# HDMI_Bridge.net
KiCad netlist of a schematic drawn in Altium Designer
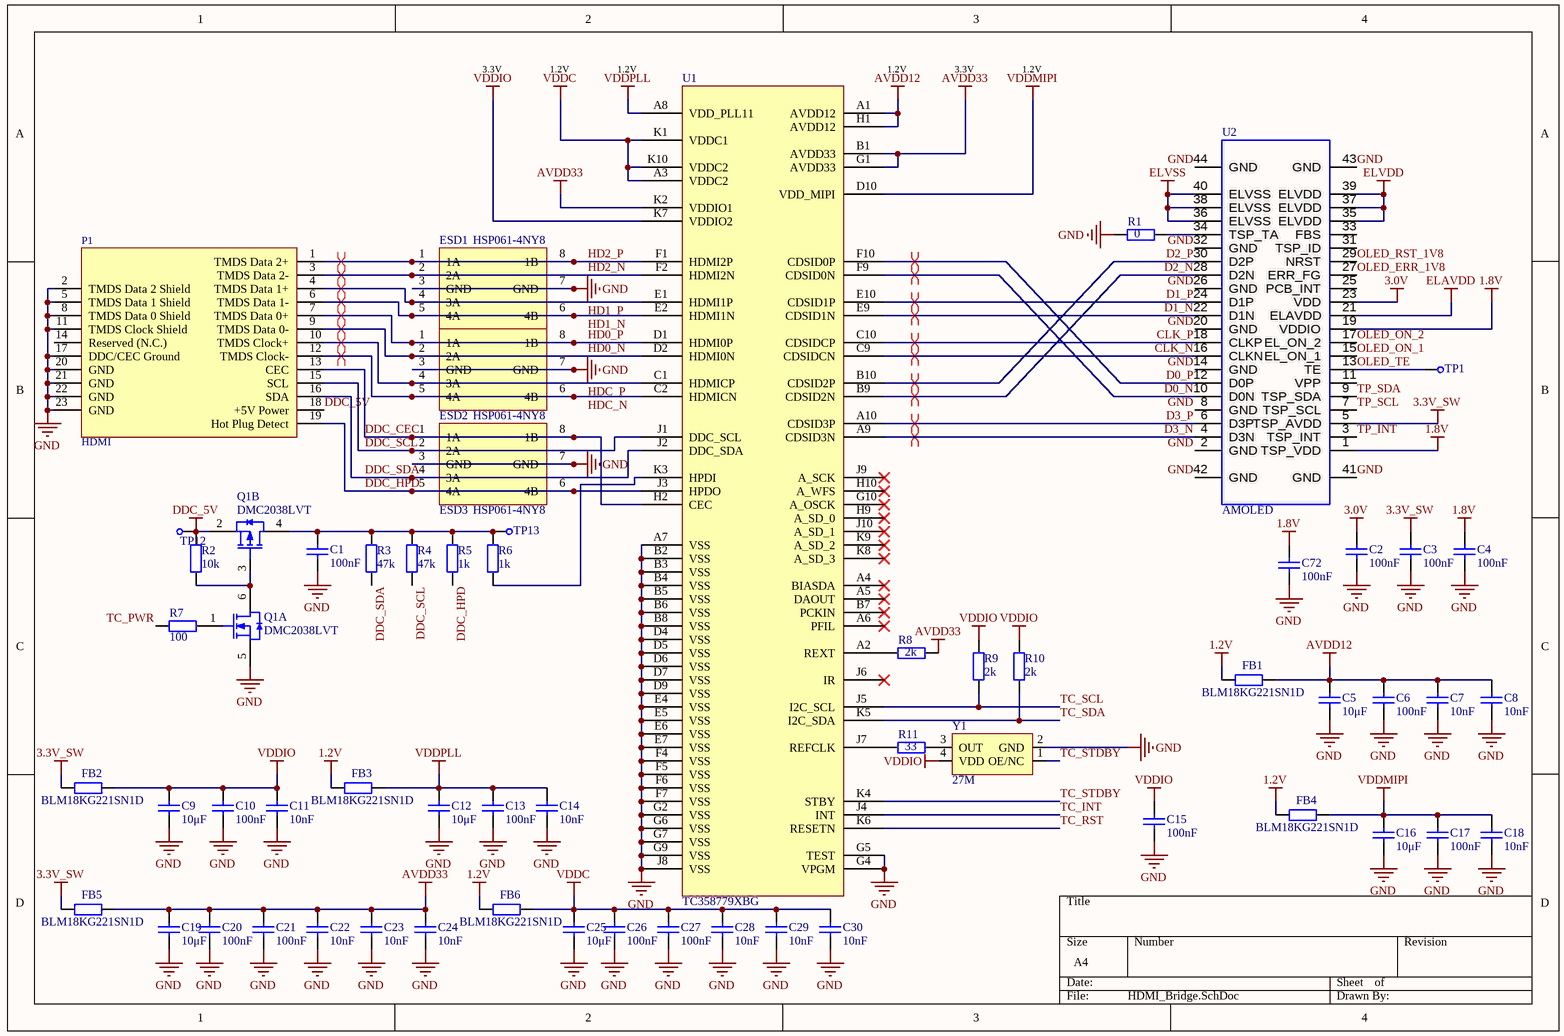
[diagram p0: HDMI_Bridge.SchDoc]

(export (version "E")
  (design (tool "Eeschema 10.0.6"))
  (components
    (comp (ref "C1")
      (value "100nF")
      (footprint "0402C")
      (description "无极性电容")
      (fields (field (name "Comment") "Cap") (field (name "PUBLISHER") "Altium Limited"))
      (libsource (lib "Huskie") (part "Cap"))
    )
    (comp (ref "C2")
      (value "100nF")
      (footprint "0402C")
      (description "无极性电容")
      (fields (field (name "Comment") "Cap") (field (name "PUBLISHER") "Altium Limited"))
      (libsource (lib "Huskie") (part "Cap"))
    )
    (comp (ref "C3")
      (value "100nF")
      (footprint "0402C")
      (description "无极性电容")
      (fields (field (name "Comment") "Cap") (field (name "PUBLISHER") "Altium Limited"))
      (libsource (lib "Huskie") (part "Cap"))
    )
    (comp (ref "C4")
      (value "100nF")
      (footprint "0402C")
      (description "无极性电容")
      (fields (field (name "Comment") "Cap") (field (name "PUBLISHER") "Altium Limited"))
      (libsource (lib "Huskie") (part "Cap"))
    )
    (comp (ref "C5")
      (value "10μF")
      (footprint "0603C")
      (description "无极性电容")
      (fields (field (name "Comment") "Cap") (field (name "PUBLISHER") "Altium Limited"))
      (libsource (lib "Huskie") (part "Cap"))
    )
    (comp (ref "C6")
      (value "100nF")
      (footprint "0402C")
      (description "无极性电容")
      (fields (field (name "Comment") "Cap") (field (name "PUBLISHER") "Altium Limited"))
      (libsource (lib "Huskie") (part "Cap"))
    )
    (comp (ref "C7")
      (value "10nF")
      (footprint "0402C")
      (description "无极性电容")
      (fields (field (name "Comment") "Cap") (field (name "PUBLISHER") "Altium Limited"))
      (libsource (lib "Huskie") (part "Cap"))
    )
    (comp (ref "C8")
      (value "10nF")
      (footprint "0402C")
      (description "无极性电容")
      (fields (field (name "Comment") "Cap") (field (name "PUBLISHER") "Altium Limited"))
      (libsource (lib "Huskie") (part "Cap"))
    )
    (comp (ref "C9")
      (value "10μF")
      (footprint "0603C")
      (description "无极性电容")
      (fields (field (name "Comment") "Cap") (field (name "PUBLISHER") "Altium Limited"))
      (libsource (lib "Huskie") (part "Cap"))
    )
    (comp (ref "C10")
      (value "100nF")
      (footprint "0402C")
      (description "无极性电容")
      (fields (field (name "Comment") "Cap") (field (name "PUBLISHER") "Altium Limited"))
      (libsource (lib "Huskie") (part "Cap"))
    )
    (comp (ref "C11")
      (value "10nF")
      (footprint "0402C")
      (description "无极性电容")
      (fields (field (name "Comment") "Cap") (field (name "PUBLISHER") "Altium Limited"))
      (libsource (lib "Huskie") (part "Cap"))
    )
    (comp (ref "C12")
      (value "10μF")
      (footprint "0603C")
      (description "无极性电容")
      (fields (field (name "Comment") "Cap") (field (name "PUBLISHER") "Altium Limited"))
      (libsource (lib "Huskie") (part "Cap"))
    )
    (comp (ref "C13")
      (value "100nF")
      (footprint "0402C")
      (description "无极性电容")
      (fields (field (name "Comment") "Cap") (field (name "PUBLISHER") "Altium Limited"))
      (libsource (lib "Huskie") (part "Cap"))
    )
    (comp (ref "C14")
      (value "10nF")
      (footprint "0402C")
      (description "无极性电容")
      (fields (field (name "Comment") "Cap") (field (name "PUBLISHER") "Altium Limited"))
      (libsource (lib "Huskie") (part "Cap"))
    )
    (comp (ref "C15")
      (value "100nF")
      (footprint "0402C")
      (description "无极性电容")
      (fields (field (name "Comment") "Cap") (field (name "PUBLISHER") "Altium Limited"))
      (libsource (lib "Huskie") (part "Cap"))
    )
    (comp (ref "C16")
      (value "10μF")
      (footprint "0603C")
      (description "无极性电容")
      (fields (field (name "Comment") "Cap") (field (name "PUBLISHER") "Altium Limited"))
      (libsource (lib "Huskie") (part "Cap"))
    )
    (comp (ref "C17")
      (value "100nF")
      (footprint "0402C")
      (description "无极性电容")
      (fields (field (name "Comment") "Cap") (field (name "PUBLISHER") "Altium Limited"))
      (libsource (lib "Huskie") (part "Cap"))
    )
    (comp (ref "C18")
      (value "10nF")
      (footprint "0402C")
      (description "无极性电容")
      (fields (field (name "Comment") "Cap") (field (name "PUBLISHER") "Altium Limited"))
      (libsource (lib "Huskie") (part "Cap"))
    )
    (comp (ref "C19")
      (value "10μF")
      (footprint "0603C")
      (description "无极性电容")
      (fields (field (name "Comment") "Cap") (field (name "PUBLISHER") "Altium Limited"))
      (libsource (lib "Huskie") (part "Cap"))
    )
    (comp (ref "C20")
      (value "100nF")
      (footprint "0402C")
      (description "无极性电容")
      (fields (field (name "Comment") "Cap") (field (name "PUBLISHER") "Altium Limited"))
      (libsource (lib "Huskie") (part "Cap"))
    )
    (comp (ref "C21")
      (value "100nF")
      (footprint "0402C")
      (description "无极性电容")
      (fields (field (name "Comment") "Cap") (field (name "PUBLISHER") "Altium Limited"))
      (libsource (lib "Huskie") (part "Cap"))
    )
    (comp (ref "C22")
      (value "10nF")
      (footprint "0402C")
      (description "无极性电容")
      (fields (field (name "Comment") "Cap") (field (name "PUBLISHER") "Altium Limited"))
      (libsource (lib "Huskie") (part "Cap"))
    )
    (comp (ref "C23")
      (value "10nF")
      (footprint "0402C")
      (description "无极性电容")
      (fields (field (name "Comment") "Cap") (field (name "PUBLISHER") "Altium Limited"))
      (libsource (lib "Huskie") (part "Cap"))
    )
    (comp (ref "C24")
      (value "10nF")
      (footprint "0402C")
      (description "无极性电容")
      (fields (field (name "Comment") "Cap") (field (name "PUBLISHER") "Altium Limited"))
      (libsource (lib "Huskie") (part "Cap"))
    )
    (comp (ref "C25")
      (value "10μF")
      (footprint "0603C")
      (description "无极性电容")
      (fields (field (name "Comment") "Cap") (field (name "PUBLISHER") "Altium Limited"))
      (libsource (lib "Huskie") (part "Cap"))
    )
    (comp (ref "C26")
      (value "100nF")
      (footprint "0402C")
      (description "无极性电容")
      (fields (field (name "Comment") "Cap") (field (name "PUBLISHER") "Altium Limited"))
      (libsource (lib "Huskie") (part "Cap"))
    )
    (comp (ref "C27")
      (value "100nF")
      (footprint "0402C")
      (description "无极性电容")
      (fields (field (name "Comment") "Cap") (field (name "PUBLISHER") "Altium Limited"))
      (libsource (lib "Huskie") (part "Cap"))
    )
    (comp (ref "C28")
      (value "10nF")
      (footprint "0402C")
      (description "无极性电容")
      (fields (field (name "Comment") "Cap") (field (name "PUBLISHER") "Altium Limited"))
      (libsource (lib "Huskie") (part "Cap"))
    )
    (comp (ref "C29")
      (value "10nF")
      (footprint "0402C")
      (description "无极性电容")
      (fields (field (name "Comment") "Cap") (field (name "PUBLISHER") "Altium Limited"))
      (libsource (lib "Huskie") (part "Cap"))
    )
    (comp (ref "C30")
      (value "10nF")
      (footprint "0402C")
      (description "无极性电容")
      (fields (field (name "Comment") "Cap") (field (name "PUBLISHER") "Altium Limited"))
      (libsource (lib "Huskie") (part "Cap"))
    )
    (comp (ref "C72")
      (value "100nF")
      (footprint "0402C")
      (description "无极性电容")
      (fields (field (name "Comment") "Cap") (field (name "PUBLISHER") "Altium Limited"))
      (libsource (lib "Huskie") (part "Cap"))
    )
    (comp (ref "ESD1")
      (value "HSP061-4NY8")
      (footprint "HSP061-4NY8")
      (description "IC, 4-LINE ESD PROTECTION ARRAY, HIGH SPEED")
      (fields (field (name "MANUFACTURER") "STMICROELECTRONICS"))
      (libsource (lib "Huskie") (part "HSP061-4NY8"))
    )
    (comp (ref "ESD2")
      (value "HSP061-4NY8")
      (footprint "HSP061-4NY8")
      (description "IC, 4-LINE ESD PROTECTION ARRAY, HIGH SPEED")
      (fields (field (name "MANUFACTURER") "STMICROELECTRONICS"))
      (libsource (lib "Huskie") (part "HSP061-4NY8"))
    )
    (comp (ref "ESD3")
      (value "HSP061-4NY8")
      (footprint "HSP061-4NY8")
      (description "IC, 4-LINE ESD PROTECTION ARRAY, HIGH SPEED")
      (fields (field (name "MANUFACTURER") "STMICROELECTRONICS"))
      (libsource (lib "Huskie") (part "HSP061-4NY8"))
    )
    (comp (ref "FB1")
      (value "BLM18KG221SN1D")
      (footprint "0603R")
      (description "电阻")
      (fields (field (name "Comment") "Resistor") (field (name "PUBLISHER") "Altium Limited"))
      (libsource (lib "Huskie") (part "Resistor"))
    )
    (comp (ref "FB2")
      (value "BLM18KG221SN1D")
      (footprint "0603R")
      (description "电阻")
      (fields (field (name "Comment") "Resistor") (field (name "PUBLISHER") "Altium Limited"))
      (libsource (lib "Huskie") (part "Resistor"))
    )
    (comp (ref "FB3")
      (value "BLM18KG221SN1D")
      (footprint "0603R")
      (description "电阻")
      (fields (field (name "Comment") "Resistor") (field (name "PUBLISHER") "Altium Limited"))
      (libsource (lib "Huskie") (part "Resistor"))
    )
    (comp (ref "FB4")
      (value "BLM18KG221SN1D")
      (footprint "0603R")
      (description "电阻")
      (fields (field (name "Comment") "Resistor") (field (name "PUBLISHER") "Altium Limited"))
      (libsource (lib "Huskie") (part "Resistor"))
    )
    (comp (ref "FB5")
      (value "BLM18KG221SN1D")
      (footprint "0603R")
      (description "电阻")
      (fields (field (name "Comment") "Resistor") (field (name "PUBLISHER") "Altium Limited"))
      (libsource (lib "Huskie") (part "Resistor"))
    )
    (comp (ref "FB6")
      (value "BLM18KG221SN1D")
      (footprint "0603R")
      (description "电阻")
      (fields (field (name "Comment") "Resistor") (field (name "PUBLISHER") "Altium Limited"))
      (libsource (lib "Huskie") (part "Resistor"))
    )
    (comp (ref "P1")
      (value "HDMI")
      (footprint "HDMI-SMD_HDMI-001S")
      (description "HDMI Slot")
      (fields
        (field (name "BOM_SUPPLIER PART") "C720616")
        (field (name "BOM_MANUFACTURER PART") "HDMI-001S")
        (field (name "CONTRIBUTOR") "LCSC")
      )
      (libsource (lib "Huskie") (part "HDMI-Slot"))
    )
    (comp (ref "Q1")
      (value "DMC2038LVT")
      (footprint "SOT-23-6")
      (description "Dual P + N MOS")
      (libsource (lib "Huskie") (part "DMC2038LVT"))
    )
    (comp (ref "R1")
      (value "0")
      (footprint "0402R")
      (description "电阻")
      (fields (field (name "Comment") "Resistor") (field (name "PUBLISHER") "Altium Limited"))
      (libsource (lib "") (part "Resistor_1"))
    )
    (comp (ref "R2")
      (value "10k")
      (footprint "0402R")
      (description "电阻")
      (fields (field (name "Comment") "Resistor") (field (name "PUBLISHER") "Altium Limited"))
      (libsource (lib "") (part "Resistor_2"))
    )
    (comp (ref "R3")
      (value "47k")
      (footprint "0402R")
      (description "电阻")
      (fields (field (name "Comment") "Resistor") (field (name "PUBLISHER") "Altium Limited"))
      (libsource (lib "") (part "Resistor_2"))
    )
    (comp (ref "R4")
      (value "47k")
      (footprint "0402R")
      (description "电阻")
      (fields (field (name "Comment") "Resistor") (field (name "PUBLISHER") "Altium Limited"))
      (libsource (lib "") (part "Resistor_2"))
    )
    (comp (ref "R5")
      (value "1k")
      (footprint "0402R")
      (description "电阻")
      (fields (field (name "Comment") "Resistor") (field (name "PUBLISHER") "Altium Limited"))
      (libsource (lib "") (part "Resistor_2"))
    )
    (comp (ref "R6")
      (value "1k")
      (footprint "0402R")
      (description "电阻")
      (fields (field (name "Comment") "Resistor") (field (name "PUBLISHER") "Altium Limited"))
      (libsource (lib "") (part "Resistor_2"))
    )
    (comp (ref "R7")
      (value "100")
      (footprint "0402R")
      (description "电阻")
      (fields (field (name "Comment") "Resistor") (field (name "PUBLISHER") "Altium Limited"))
      (libsource (lib "Huskie") (part "Resistor"))
    )
    (comp (ref "R8")
      (value "2k")
      (footprint "0402R")
      (description "电阻")
      (fields (field (name "Comment") "Resistor") (field (name "PUBLISHER") "Altium Limited"))
      (libsource (lib "") (part "Resistor_1"))
    )
    (comp (ref "R9")
      (value "2k")
      (footprint "0402R")
      (description "电阻")
      (fields (field (name "Comment") "Resistor") (field (name "PUBLISHER") "Altium Limited"))
      (libsource (lib "") (part "Resistor_2"))
    )
    (comp (ref "R10")
      (value "2k")
      (footprint "0402R")
      (description "电阻")
      (fields (field (name "Comment") "Resistor") (field (name "PUBLISHER") "Altium Limited"))
      (libsource (lib "") (part "Resistor_2"))
    )
    (comp (ref "R11")
      (value "33")
      (footprint "0402R")
      (description "电阻")
      (fields (field (name "Comment") "Resistor") (field (name "PUBLISHER") "Altium Limited"))
      (libsource (lib "") (part "Resistor_1"))
    )
    (comp (ref "TP1")
      (value "CHECK")
      (footprint "CHECK-B")
      (description "测试点")
      (libsource (lib "Huskie") (part "CHECK"))
    )
    (comp (ref "TP12")
      (value "CHECK")
      (footprint "CHECK-B")
      (description "测试点")
      (libsource (lib "Huskie") (part "CHECK"))
    )
    (comp (ref "TP13")
      (value "CHECK")
      (footprint "CHECK-B")
      (description "测试点")
      (libsource (lib "Huskie") (part "CHECK"))
    )
    (comp (ref "U1")
      (value "TC358779XBG")
      (footprint "BGA-80_L7.0-W7.0-R10-C10-P0.65-TL")
      (description "IC, HDMI RX TO MIPI DSI TX BRIDGE")
      (fields (field (name "MANUFACTURER") "TOSHIBA"))
      (libsource (lib "Huskie") (part "TC358779XBG"))
    )
    (comp (ref "U2")
      (value "AMOLED")
      (footprint "BTB_AXE440124")
      (description "SAMSUNG AMOLED, CONNECTOR AXE440124, 40-PIN HEADER, 0.4MM PITCH")
      (fields (field (name "MANUFACTURER") "PANASONIC") (field (name "PART NUMBER") "AXE440124"))
      (libsource (lib "Huskie") (part "OLED_AMS568"))
    )
    (comp (ref "Y1")
      (value "27M")
      (footprint "XTAL-3225-4P")
      (description "贴片有源晶振")
      (fields (field (name "Comment") "XATLS"))
      (libsource (lib "Huskie") (part "XATL-OSC"))
    )
  )
  (nets
    (net (code "1") (name "/CLK_N") (class "Default")
      (node (ref "U1") (pin "C9") (pinfunction "CDSIDCN_C9") (pintype "passive"))
      (node (ref "U2") (pin "16") (pinfunction "CLKN_16") (pintype "passive"))
    )
    (net (code "2") (name "/CLK_P") (class "Default")
      (node (ref "U1") (pin "C10") (pinfunction "CDSIDCP_C10") (pintype "passive"))
      (node (ref "U2") (pin "18") (pinfunction "CLKP_18") (pintype "passive"))
    )
    (net (code "3") (name "/D0_N") (class "Default")
      (node (ref "U1") (pin "F9") (pinfunction "CDSID0N_F9") (pintype "passive"))
      (node (ref "U2") (pin "10") (pinfunction "D0N_10") (pintype "passive"))
    )
    (net (code "4") (name "/D0_P") (class "Default")
      (node (ref "U1") (pin "F10") (pinfunction "CDSID0P_F10") (pintype "passive"))
      (node (ref "U2") (pin "12") (pinfunction "D0P_12") (pintype "passive"))
    )
    (net (code "5") (name "/D1_N") (class "Default")
      (node (ref "U1") (pin "E9") (pinfunction "CDSID1N_E9") (pintype "passive"))
      (node (ref "U2") (pin "22") (pinfunction "D1N_22") (pintype "passive"))
    )
    (net (code "6") (name "/D1_P") (class "Default")
      (node (ref "U1") (pin "E10") (pinfunction "CDSID1P_E10") (pintype "passive"))
      (node (ref "U2") (pin "24") (pinfunction "D1P_24") (pintype "passive"))
    )
    (net (code "7") (name "/D2_N") (class "Default")
      (node (ref "U1") (pin "B9") (pinfunction "CDSID2N_B9") (pintype "passive"))
      (node (ref "U2") (pin "28") (pinfunction "D2N_28") (pintype "passive"))
    )
    (net (code "8") (name "/D2_P") (class "Default")
      (node (ref "U1") (pin "B10") (pinfunction "CDSID2P_B10") (pintype "passive"))
      (node (ref "U2") (pin "30") (pinfunction "D2P_30") (pintype "passive"))
    )
    (net (code "9") (name "/D3_N") (class "Default")
      (node (ref "U1") (pin "A9") (pinfunction "CDSID3N_A9") (pintype "passive"))
      (node (ref "U2") (pin "4") (pinfunction "D3N_4") (pintype "passive"))
    )
    (net (code "10") (name "/D3_P") (class "Default")
      (node (ref "U1") (pin "A10") (pinfunction "CDSID3P_A10") (pintype "passive"))
      (node (ref "U2") (pin "6") (pinfunction "D3P_6") (pintype "passive"))
    )
    (net (code "11") (name "/DDC_CEC") (class "Default")
      (node (ref "ESD3") (pin "1") (pinfunction "1A_1") (pintype "passive"))
      (node (ref "ESD3") (pin "8") (pinfunction "1B_8") (pintype "passive"))
      (node (ref "P1") (pin "13") (pinfunction "CEC_13") (pintype "passive"))
      (node (ref "U1") (pin "H2") (pinfunction "CEC_H2") (pintype "passive"))
    )
    (net (code "12") (name "/DDC_HPD") (class "Default")
      (node (ref "ESD3") (pin "5") (pinfunction "4A_5") (pintype "passive"))
      (node (ref "ESD3") (pin "6") (pinfunction "4B_6") (pintype "passive"))
      (node (ref "P1") (pin "19") (pinfunction "Hot_Plug_Detect_19") (pintype "passive"))
      (node (ref "R5") (pin "2") (pinfunction "2_2") (pintype "passive"))
      (node (ref "U1") (pin "J3") (pinfunction "HPDO_J3") (pintype "passive"))
    )
    (net (code "13") (name "/DDC_SCL") (class "Default")
      (node (ref "ESD3") (pin "2") (pinfunction "2A_2") (pintype "passive"))
      (node (ref "P1") (pin "15") (pinfunction "SCL_15") (pintype "passive"))
      (node (ref "R4") (pin "2") (pinfunction "2_2") (pintype "passive"))
      (node (ref "U1") (pin "J1") (pinfunction "DDC_SCL_J1") (pintype "passive"))
    )
    (net (code "14") (name "/DDC_SDA") (class "Default")
      (node (ref "ESD3") (pin "4") (pinfunction "3A_4") (pintype "passive"))
      (node (ref "P1") (pin "16") (pinfunction "SDA_16") (pintype "passive"))
      (node (ref "R3") (pin "2") (pinfunction "2_2") (pintype "passive"))
      (node (ref "U1") (pin "J2") (pinfunction "DDC_SDA_J2") (pintype "passive"))
    )
    (net (code "15") (name "/HD0_N") (class "Default")
      (node (ref "ESD2") (pin "2") (pinfunction "2A_2") (pintype "passive"))
      (node (ref "P1") (pin "9") (pinfunction "TMDS_Data_0-_9") (pintype "passive"))
      (node (ref "U1") (pin "D2") (pinfunction "HDMI0N_D2") (pintype "passive"))
    )
    (net (code "16") (name "/HD0_P") (class "Default")
      (node (ref "ESD2") (pin "1") (pinfunction "1A_1") (pintype "passive"))
      (node (ref "ESD2") (pin "8") (pinfunction "1B_8") (pintype "passive"))
      (node (ref "P1") (pin "7") (pinfunction "TMDS_Data_0+_7") (pintype "passive"))
      (node (ref "U1") (pin "D1") (pinfunction "HDMI0P_D1") (pintype "passive"))
    )
    (net (code "17") (name "/HD1_N") (class "Default")
      (node (ref "ESD1") (pin "5") (pinfunction "4A_5") (pintype "passive"))
      (node (ref "ESD1") (pin "6") (pinfunction "4B_6") (pintype "passive"))
      (node (ref "P1") (pin "6") (pinfunction "TMDS_Data_1-_6") (pintype "passive"))
      (node (ref "U1") (pin "E2") (pinfunction "HDMI1N_E2") (pintype "passive"))
    )
    (net (code "18") (name "/HD1_P") (class "Default")
      (node (ref "ESD1") (pin "4") (pinfunction "3A_4") (pintype "passive"))
      (node (ref "P1") (pin "4") (pinfunction "TMDS_Data_1+_4") (pintype "passive"))
      (node (ref "U1") (pin "E1") (pinfunction "HDMI1P_E1") (pintype "passive"))
    )
    (net (code "19") (name "/HD2_N") (class "Default")
      (node (ref "ESD1") (pin "2") (pinfunction "2A_2") (pintype "passive"))
      (node (ref "P1") (pin "3") (pinfunction "TMDS_Data_2-_3") (pintype "passive"))
      (node (ref "U1") (pin "F2") (pinfunction "HDMI2N_F2") (pintype "passive"))
    )
    (net (code "20") (name "/HD2_P") (class "Default")
      (node (ref "ESD1") (pin "1") (pinfunction "1A_1") (pintype "passive"))
      (node (ref "ESD1") (pin "8") (pinfunction "1B_8") (pintype "passive"))
      (node (ref "P1") (pin "1") (pinfunction "TMDS_Data_2+_1") (pintype "passive"))
      (node (ref "U1") (pin "F1") (pinfunction "HDMI2P_F1") (pintype "passive"))
    )
    (net (code "21") (name "/HDC_N") (class "Default")
      (node (ref "ESD2") (pin "5") (pinfunction "4A_5") (pintype "passive"))
      (node (ref "ESD2") (pin "6") (pinfunction "4B_6") (pintype "passive"))
      (node (ref "P1") (pin "12") (pinfunction "TMDS_Clock-_12") (pintype "passive"))
      (node (ref "U1") (pin "C2") (pinfunction "HDMICN_C2") (pintype "passive"))
    )
    (net (code "22") (name "/HDC_P") (class "Default")
      (node (ref "ESD2") (pin "4") (pinfunction "3A_4") (pintype "passive"))
      (node (ref "P1") (pin "10") (pinfunction "TMDS_Clock+_10") (pintype "passive"))
      (node (ref "U1") (pin "C1") (pinfunction "HDMICP_C1") (pintype "passive"))
    )
    (net (code "23") (name "/OLED_ERR_1V8") (class "Default")
      (node (ref "U2") (pin "27") (pinfunction "ERR_FG_27") (pintype "passive"))
    )
    (net (code "24") (name "/OLED_ON_1") (class "Default")
      (node (ref "U2") (pin "15") (pinfunction "EL_ON_1_15") (pintype "passive"))
    )
    (net (code "25") (name "/OLED_ON_2") (class "Default")
      (node (ref "U2") (pin "17") (pinfunction "EL_ON_2_17") (pintype "passive"))
    )
    (net (code "26") (name "/OLED_RST_1V8") (class "Default")
      (node (ref "U2") (pin "29") (pinfunction "NRST_29") (pintype "passive"))
    )
    (net (code "27") (name "/OLED_TE") (class "Default")
      (node (ref "TP1") (pin "1") (pinfunction "1_1") (pintype "passive"))
      (node (ref "U2") (pin "13") (pinfunction "TE_13") (pintype "passive"))
    )
    (net (code "28") (name "/TC_INT") (class "Default")
      (node (ref "U1") (pin "J4") (pinfunction "INT_J4") (pintype "passive"))
    )
    (net (code "29") (name "/TC_PWR") (class "Default")
      (node (ref "R7") (pin "1") (pinfunction "1_1") (pintype "passive"))
    )
    (net (code "30") (name "/TC_RST") (class "Default")
      (node (ref "U1") (pin "K6") (pinfunction "RESETN_K6") (pintype "passive"))
    )
    (net (code "31") (name "/TC_SCL") (class "Default")
      (node (ref "R9") (pin "2") (pinfunction "2_2") (pintype "passive"))
      (node (ref "U1") (pin "J5") (pinfunction "I2C_SCL_J5") (pintype "passive"))
    )
    (net (code "32") (name "/TC_SDA") (class "Default")
      (node (ref "R10") (pin "2") (pinfunction "2_2") (pintype "passive"))
      (node (ref "U1") (pin "K5") (pinfunction "I2C_SDA_K5") (pintype "passive"))
    )
    (net (code "33") (name "/TC_STDBY") (class "Default")
      (node (ref "U1") (pin "K4") (pinfunction "STBY_K4") (pintype "passive"))
      (node (ref "Y1") (pin "1") (pinfunction "OE/NC_1") (pintype "passive"))
    )
    (net (code "34") (name "/TP_INT") (class "Default")
      (node (ref "U2") (pin "3") (pinfunction "TSP_INT_3") (pintype "passive"))
    )
    (net (code "35") (name "/TP_SCL") (class "Default")
      (node (ref "U2") (pin "7") (pinfunction "TSP_SCL_7") (pintype "passive"))
    )
    (net (code "36") (name "/TP_SDA") (class "Default")
      (node (ref "U2") (pin "9") (pinfunction "TSP_SDA_9") (pintype "passive"))
    )
    (net (code "37") (name "1.2V") (class "Default")
      (node (ref "FB1") (pin "1") (pinfunction "1_1") (pintype "passive"))
      (node (ref "FB3") (pin "1") (pinfunction "1_1") (pintype "passive"))
      (node (ref "FB4") (pin "1") (pinfunction "1_1") (pintype "passive"))
      (node (ref "FB6") (pin "1") (pinfunction "1_1") (pintype "passive"))
    )
    (net (code "38") (name "1.8V") (class "Default")
      (node (ref "C4") (pin "2") (pinfunction "2_2") (pintype "passive"))
      (node (ref "C72") (pin "2") (pinfunction "2_2") (pintype "passive"))
      (node (ref "U2") (pin "1") (pinfunction "TSP_VDD_1") (pintype "passive"))
      (node (ref "U2") (pin "19") (pinfunction "VDDIO_19") (pintype "passive"))
    )
    (net (code "39") (name "3.0V") (class "Default")
      (node (ref "C2") (pin "2") (pinfunction "2_2") (pintype "passive"))
      (node (ref "U2") (pin "23") (pinfunction "VDD_23") (pintype "passive"))
    )
    (net (code "40") (name "3.3V_SW") (class "Default")
      (node (ref "C3") (pin "2") (pinfunction "2_2") (pintype "passive"))
      (node (ref "FB2") (pin "1") (pinfunction "1_1") (pintype "passive"))
      (node (ref "FB5") (pin "1") (pinfunction "1_1") (pintype "passive"))
      (node (ref "U2") (pin "5") (pinfunction "TSP_AVDD_5") (pintype "passive"))
    )
    (net (code "41") (name "AVDD12") (class "Default")
      (node (ref "C5") (pin "2") (pinfunction "2_2") (pintype "passive"))
      (node (ref "C6") (pin "2") (pinfunction "2_2") (pintype "passive"))
      (node (ref "C7") (pin "2") (pinfunction "2_2") (pintype "passive"))
      (node (ref "C8") (pin "2") (pinfunction "2_2") (pintype "passive"))
      (node (ref "FB1") (pin "2") (pinfunction "2_2") (pintype "passive"))
      (node (ref "U1") (pin "A1") (pinfunction "AVDD12_A1") (pintype "passive"))
      (node (ref "U1") (pin "H1") (pinfunction "AVDD12_H1") (pintype "passive"))
    )
    (net (code "42") (name "AVDD33") (class "Default")
      (node (ref "C19") (pin "2") (pinfunction "2_2") (pintype "passive"))
      (node (ref "C20") (pin "2") (pinfunction "2_2") (pintype "passive"))
      (node (ref "C21") (pin "2") (pinfunction "2_2") (pintype "passive"))
      (node (ref "C22") (pin "2") (pinfunction "2_2") (pintype "passive"))
      (node (ref "C23") (pin "2") (pinfunction "2_2") (pintype "passive"))
      (node (ref "C24") (pin "2") (pinfunction "2_2") (pintype "passive"))
      (node (ref "FB5") (pin "2") (pinfunction "2_2") (pintype "passive"))
      (node (ref "R8") (pin "1") (pinfunction "1_1") (pintype "passive"))
      (node (ref "U1") (pin "B1") (pinfunction "AVDD33_B1") (pintype "passive"))
      (node (ref "U1") (pin "G1") (pinfunction "AVDD33_G1") (pintype "passive"))
      (node (ref "U1") (pin "K2") (pinfunction "VDDIO1_K2") (pintype "passive"))
    )
    (net (code "43") (name "DDC_5V") (class "Default")
      (node (ref "P1") (pin "18") (pinfunction "+5V_Power_18") (pintype "passive"))
      (node (ref "Q1") (pin "2") (pinfunction "S_2") (pintype "passive"))
      (node (ref "R2") (pin "1") (pinfunction "1_1") (pintype "passive"))
      (node (ref "TP12") (pin "1") (pinfunction "1_1") (pintype "passive"))
    )
    (net (code "44") (name "ELAVDD") (class "Default")
      (node (ref "U2") (pin "21") (pinfunction "ELAVDD_21") (pintype "passive"))
    )
    (net (code "45") (name "ELVDD") (class "Default")
      (node (ref "U2") (pin "35") (pinfunction "ELVDD_35") (pintype "passive"))
      (node (ref "U2") (pin "37") (pinfunction "ELVDD_37") (pintype "passive"))
      (node (ref "U2") (pin "39") (pinfunction "ELVDD_39") (pintype "passive"))
    )
    (net (code "46") (name "ELVSS") (class "Default")
      (node (ref "U2") (pin "36") (pinfunction "ELVSS_36") (pintype "passive"))
      (node (ref "U2") (pin "38") (pinfunction "ELVSS_38") (pintype "passive"))
      (node (ref "U2") (pin "40") (pinfunction "ELVSS_40") (pintype "passive"))
    )
    (net (code "47") (name "GND") (class "Default")
      (node (ref "C1") (pin "1") (pinfunction "1_1") (pintype "passive"))
      (node (ref "C10") (pin "1") (pinfunction "1_1") (pintype "passive"))
      (node (ref "C11") (pin "1") (pinfunction "1_1") (pintype "passive"))
      (node (ref "C12") (pin "1") (pinfunction "1_1") (pintype "passive"))
      (node (ref "C13") (pin "1") (pinfunction "1_1") (pintype "passive"))
      (node (ref "C14") (pin "1") (pinfunction "1_1") (pintype "passive"))
      (node (ref "C15") (pin "1") (pinfunction "1_1") (pintype "passive"))
      (node (ref "C16") (pin "1") (pinfunction "1_1") (pintype "passive"))
      (node (ref "C17") (pin "1") (pinfunction "1_1") (pintype "passive"))
      (node (ref "C18") (pin "1") (pinfunction "1_1") (pintype "passive"))
      (node (ref "C19") (pin "1") (pinfunction "1_1") (pintype "passive"))
      (node (ref "C2") (pin "1") (pinfunction "1_1") (pintype "passive"))
      (node (ref "C20") (pin "1") (pinfunction "1_1") (pintype "passive"))
      (node (ref "C21") (pin "1") (pinfunction "1_1") (pintype "passive"))
      (node (ref "C22") (pin "1") (pinfunction "1_1") (pintype "passive"))
      (node (ref "C23") (pin "1") (pinfunction "1_1") (pintype "passive"))
      (node (ref "C24") (pin "1") (pinfunction "1_1") (pintype "passive"))
      (node (ref "C25") (pin "1") (pinfunction "1_1") (pintype "passive"))
      (node (ref "C26") (pin "1") (pinfunction "1_1") (pintype "passive"))
      (node (ref "C27") (pin "1") (pinfunction "1_1") (pintype "passive"))
      (node (ref "C28") (pin "1") (pinfunction "1_1") (pintype "passive"))
      (node (ref "C29") (pin "1") (pinfunction "1_1") (pintype "passive"))
      (node (ref "C3") (pin "1") (pinfunction "1_1") (pintype "passive"))
      (node (ref "C30") (pin "1") (pinfunction "1_1") (pintype "passive"))
      (node (ref "C4") (pin "1") (pinfunction "1_1") (pintype "passive"))
      (node (ref "C5") (pin "1") (pinfunction "1_1") (pintype "passive"))
      (node (ref "C6") (pin "1") (pinfunction "1_1") (pintype "passive"))
      (node (ref "C7") (pin "1") (pinfunction "1_1") (pintype "passive"))
      (node (ref "C72") (pin "1") (pinfunction "1_1") (pintype "passive"))
      (node (ref "C8") (pin "1") (pinfunction "1_1") (pintype "passive"))
      (node (ref "C9") (pin "1") (pinfunction "1_1") (pintype "passive"))
      (node (ref "ESD1") (pin "3") (pinfunction "GND_3") (pintype "power_in"))
      (node (ref "ESD1") (pin "7") (pinfunction "GND_7") (pintype "power_in"))
      (node (ref "ESD2") (pin "3") (pinfunction "GND_3") (pintype "power_in"))
      (node (ref "ESD2") (pin "7") (pinfunction "GND_7") (pintype "power_in"))
      (node (ref "ESD3") (pin "3") (pinfunction "GND_3") (pintype "power_in"))
      (node (ref "ESD3") (pin "7") (pinfunction "GND_7") (pintype "power_in"))
      (node (ref "P1") (pin "11") (pinfunction "TMDS_Clock_Shield_11") (pintype "passive"))
      (node (ref "P1") (pin "17") (pinfunction "DDC/CEC_Ground_17") (pintype "passive"))
      (node (ref "P1") (pin "2") (pinfunction "TMDS_Data_2_Shield_2") (pintype "passive"))
      (node (ref "P1") (pin "20") (pinfunction "GND_20") (pintype "passive"))
      (node (ref "P1") (pin "21") (pinfunction "GND_21") (pintype "passive"))
      (node (ref "P1") (pin "22") (pinfunction "GND_22") (pintype "passive"))
      (node (ref "P1") (pin "23") (pinfunction "GND_23") (pintype "passive"))
      (node (ref "P1") (pin "5") (pinfunction "TMDS_Data_1_Shield_5") (pintype "passive"))
      (node (ref "P1") (pin "8") (pinfunction "TMDS_Data_0_Shield_8") (pintype "passive"))
      (node (ref "Q1") (pin "5") (pinfunction "S_5") (pintype "passive"))
      (node (ref "R1") (pin "2") (pinfunction "2_2") (pintype "passive"))
      (node (ref "U1") (pin "A7") (pinfunction "VSS_A7") (pintype "passive"))
      (node (ref "U1") (pin "B2") (pinfunction "VSS_B2") (pintype "passive"))
      (node (ref "U1") (pin "B3") (pinfunction "VSS_B3") (pintype "passive"))
      (node (ref "U1") (pin "B4") (pinfunction "VSS_B4") (pintype "passive"))
      (node (ref "U1") (pin "B5") (pinfunction "VSS_B5") (pintype "passive"))
      (node (ref "U1") (pin "B6") (pinfunction "VSS_B6") (pintype "passive"))
      (node (ref "U1") (pin "B8") (pinfunction "VSS_B8") (pintype "passive"))
      (node (ref "U1") (pin "D4") (pinfunction "VSS_D4") (pintype "passive"))
      (node (ref "U1") (pin "D5") (pinfunction "VSS_D5") (pintype "passive"))
      (node (ref "U1") (pin "D6") (pinfunction "VSS_D6") (pintype "passive"))
      (node (ref "U1") (pin "D7") (pinfunction "VSS_D7") (pintype "passive"))
      (node (ref "U1") (pin "D9") (pinfunction "VSS_D9") (pintype "passive"))
      (node (ref "U1") (pin "E4") (pinfunction "VSS_E4") (pintype "passive"))
      (node (ref "U1") (pin "E5") (pinfunction "VSS_E5") (pintype "passive"))
      (node (ref "U1") (pin "E6") (pinfunction "VSS_E6") (pintype "passive"))
      (node (ref "U1") (pin "E7") (pinfunction "VSS_E7") (pintype "passive"))
      (node (ref "U1") (pin "F4") (pinfunction "VSS_F4") (pintype "passive"))
      (node (ref "U1") (pin "F5") (pinfunction "VSS_F5") (pintype "passive"))
      (node (ref "U1") (pin "F6") (pinfunction "VSS_F6") (pintype "passive"))
      (node (ref "U1") (pin "F7") (pinfunction "VSS_F7") (pintype "passive"))
      (node (ref "U1") (pin "G2") (pinfunction "VSS_G2") (pintype "passive"))
      (node (ref "U1") (pin "G4") (pinfunction "VPGM_G4") (pintype "passive"))
      (node (ref "U1") (pin "G5") (pinfunction "TEST_G5") (pintype "passive"))
      (node (ref "U1") (pin "G6") (pinfunction "VSS_G6") (pintype "passive"))
      (node (ref "U1") (pin "G7") (pinfunction "VSS_G7") (pintype "passive"))
      (node (ref "U1") (pin "G9") (pinfunction "VSS_G9") (pintype "passive"))
      (node (ref "U1") (pin "J8") (pinfunction "VSS_J8") (pintype "passive"))
      (node (ref "U2") (pin "14") (pinfunction "GND_14") (pintype "passive"))
      (node (ref "U2") (pin "2") (pinfunction "GND_2") (pintype "passive"))
      (node (ref "U2") (pin "20") (pinfunction "GND_20") (pintype "passive"))
      (node (ref "U2") (pin "26") (pinfunction "GND_26") (pintype "passive"))
      (node (ref "U2") (pin "32") (pinfunction "GND_32") (pintype "passive"))
      (node (ref "U2") (pin "41") (pinfunction "GND_41") (pintype "power_in"))
      (node (ref "U2") (pin "42") (pinfunction "GND_42") (pintype "power_in"))
      (node (ref "U2") (pin "43") (pinfunction "GND_43") (pintype "power_in"))
      (node (ref "U2") (pin "44") (pinfunction "GND_44") (pintype "power_in"))
      (node (ref "U2") (pin "8") (pinfunction "GND_8") (pintype "passive"))
      (node (ref "Y1") (pin "2") (pinfunction "GND_2") (pintype "passive"))
    )
    (net (code "48") (name "Net-(Q1A-D)") (class "Default")
      (node (ref "Q1") (pin "3") (pinfunction "G_3") (pintype "passive"))
      (node (ref "Q1") (pin "6") (pinfunction "D_6") (pintype "passive"))
      (node (ref "R2") (pin "2") (pinfunction "2_2") (pintype "passive"))
    )
    (net (code "49") (name "Net-(Q1A-G)") (class "Default")
      (node (ref "Q1") (pin "1") (pinfunction "G_1") (pintype "passive"))
      (node (ref "R7") (pin "2") (pinfunction "2_2") (pintype "passive"))
    )
    (net (code "50") (name "Net-(Q1B-D)") (class "Default")
      (node (ref "C1") (pin "2") (pinfunction "2_2") (pintype "passive"))
      (node (ref "Q1") (pin "4") (pinfunction "D_4") (pintype "passive"))
      (node (ref "R3") (pin "1") (pinfunction "1_1") (pintype "passive"))
      (node (ref "R4") (pin "1") (pinfunction "1_1") (pintype "passive"))
      (node (ref "R5") (pin "1") (pinfunction "1_1") (pintype "passive"))
      (node (ref "R6") (pin "1") (pinfunction "1_1") (pintype "passive"))
      (node (ref "TP13") (pin "1") (pinfunction "1_1") (pintype "passive"))
    )
    (net (code "51") (name "Net-(U1-HPDI)") (class "Default")
      (node (ref "R6") (pin "2") (pinfunction "2_2") (pintype "passive"))
      (node (ref "U1") (pin "K3") (pinfunction "HPDI_K3") (pintype "passive"))
    )
    (net (code "52") (name "Net-(U1-REFCLK)") (class "Default")
      (node (ref "R11") (pin "2") (pinfunction "2_2") (pintype "passive"))
      (node (ref "U1") (pin "J7") (pinfunction "REFCLK_J7") (pintype "passive"))
    )
    (net (code "53") (name "Net-(U1-REXT)") (class "Default")
      (node (ref "R8") (pin "2") (pinfunction "2_2") (pintype "passive"))
      (node (ref "U1") (pin "A2") (pinfunction "REXT_A2") (pintype "passive"))
    )
    (net (code "54") (name "Net-(U2-TSP_TA)") (class "Default")
      (node (ref "R1") (pin "1") (pinfunction "1_1") (pintype "passive"))
      (node (ref "U2") (pin "34") (pinfunction "TSP_TA_34") (pintype "passive"))
    )
    (net (code "55") (name "Net-(Y1-OUT)") (class "Default")
      (node (ref "R11") (pin "1") (pinfunction "1_1") (pintype "passive"))
      (node (ref "Y1") (pin "3") (pinfunction "OUT_3") (pintype "passive"))
    )
    (net (code "56") (name "VDDC") (class "Default")
      (node (ref "C25") (pin "2") (pinfunction "2_2") (pintype "passive"))
      (node (ref "C26") (pin "2") (pinfunction "2_2") (pintype "passive"))
      (node (ref "C27") (pin "2") (pinfunction "2_2") (pintype "passive"))
      (node (ref "C28") (pin "2") (pinfunction "2_2") (pintype "passive"))
      (node (ref "C29") (pin "2") (pinfunction "2_2") (pintype "passive"))
      (node (ref "C30") (pin "2") (pinfunction "2_2") (pintype "passive"))
      (node (ref "FB6") (pin "2") (pinfunction "2_2") (pintype "passive"))
      (node (ref "U1") (pin "A3") (pinfunction "VDDC2_A3") (pintype "passive"))
      (node (ref "U1") (pin "K1") (pinfunction "VDDC1_K1") (pintype "passive"))
      (node (ref "U1") (pin "K10") (pinfunction "VDDC2_K10") (pintype "passive"))
    )
    (net (code "57") (name "VDDIO") (class "Default")
      (node (ref "C10") (pin "2") (pinfunction "2_2") (pintype "passive"))
      (node (ref "C11") (pin "2") (pinfunction "2_2") (pintype "passive"))
      (node (ref "C15") (pin "2") (pinfunction "2_2") (pintype "passive"))
      (node (ref "C9") (pin "2") (pinfunction "2_2") (pintype "passive"))
      (node (ref "FB2") (pin "2") (pinfunction "2_2") (pintype "passive"))
      (node (ref "R10") (pin "1") (pinfunction "1_1") (pintype "passive"))
      (node (ref "R9") (pin "1") (pinfunction "1_1") (pintype "passive"))
      (node (ref "U1") (pin "K7") (pinfunction "VDDIO2_K7") (pintype "passive"))
      (node (ref "Y1") (pin "4") (pinfunction "VDD_4") (pintype "passive"))
    )
    (net (code "58") (name "VDDMIPI") (class "Default")
      (node (ref "C16") (pin "2") (pinfunction "2_2") (pintype "passive"))
      (node (ref "C17") (pin "2") (pinfunction "2_2") (pintype "passive"))
      (node (ref "C18") (pin "2") (pinfunction "2_2") (pintype "passive"))
      (node (ref "FB4") (pin "2") (pinfunction "2_2") (pintype "passive"))
      (node (ref "U1") (pin "D10") (pinfunction "VDD_MIPI_D10") (pintype "passive"))
    )
    (net (code "59") (name "VDDPLL") (class "Default")
      (node (ref "C12") (pin "2") (pinfunction "2_2") (pintype "passive"))
      (node (ref "C13") (pin "2") (pinfunction "2_2") (pintype "passive"))
      (node (ref "C14") (pin "2") (pinfunction "2_2") (pintype "passive"))
      (node (ref "FB3") (pin "2") (pinfunction "2_2") (pintype "passive"))
      (node (ref "U1") (pin "A8") (pinfunction "VDD_PLL11_A8") (pintype "passive"))
    )
    (net (code "60") (name "unconnected-(P1-Reserved_(N.C.)-Pad14)") (class "Default")
      (node (ref "P1") (pin "14") (pinfunction "Reserved_(N.C.)_14") (pintype "passive"))
    )
    (net (code "61") (name "unconnected-(U1-A_OSCK-PadG10)") (class "Default")
      (node (ref "U1") (pin "G10") (pinfunction "A_OSCK_G10") (pintype "passive+no_connect"))
    )
    (net (code "62") (name "unconnected-(U1-A_SCK-PadJ9)") (class "Default")
      (node (ref "U1") (pin "J9") (pinfunction "A_SCK_J9") (pintype "passive+no_connect"))
    )
    (net (code "63") (name "unconnected-(U1-A_SD_0-PadH9)") (class "Default")
      (node (ref "U1") (pin "H9") (pinfunction "A_SD_0_H9") (pintype "passive+no_connect"))
    )
    (net (code "64") (name "unconnected-(U1-A_SD_1-PadJ10)") (class "Default")
      (node (ref "U1") (pin "J10") (pinfunction "A_SD_1_J10") (pintype "passive+no_connect"))
    )
    (net (code "65") (name "unconnected-(U1-A_SD_2-PadK9)") (class "Default")
      (node (ref "U1") (pin "K9") (pinfunction "A_SD_2_K9") (pintype "passive+no_connect"))
    )
    (net (code "66") (name "unconnected-(U1-A_SD_3-PadK8)") (class "Default")
      (node (ref "U1") (pin "K8") (pinfunction "A_SD_3_K8") (pintype "passive+no_connect"))
    )
    (net (code "67") (name "unconnected-(U1-A_WFS-PadH10)") (class "Default")
      (node (ref "U1") (pin "H10") (pinfunction "A_WFS_H10") (pintype "passive+no_connect"))
    )
    (net (code "68") (name "unconnected-(U1-BIASDA-PadA4)") (class "Default")
      (node (ref "U1") (pin "A4") (pinfunction "BIASDA_A4") (pintype "passive+no_connect"))
    )
    (net (code "69") (name "unconnected-(U1-DAOUT-PadA5)") (class "Default")
      (node (ref "U1") (pin "A5") (pinfunction "DAOUT_A5") (pintype "passive+no_connect"))
    )
    (net (code "70") (name "unconnected-(U1-IR-PadJ6)") (class "Default")
      (node (ref "U1") (pin "J6") (pinfunction "IR_J6") (pintype "passive+no_connect"))
    )
    (net (code "71") (name "unconnected-(U1-PCKIN-PadB7)") (class "Default")
      (node (ref "U1") (pin "B7") (pinfunction "PCKIN_B7") (pintype "passive+no_connect"))
    )
    (net (code "72") (name "unconnected-(U1-PFIL-PadA6)") (class "Default")
      (node (ref "U1") (pin "A6") (pinfunction "PFIL_A6") (pintype "passive+no_connect"))
    )
    (net (code "73") (name "unconnected-(U2-FBS-Pad33)") (class "Default")
      (node (ref "U2") (pin "33") (pinfunction "FBS_33") (pintype "passive"))
    )
    (net (code "74") (name "unconnected-(U2-PCB_INT-Pad25)") (class "Default")
      (node (ref "U2") (pin "25") (pinfunction "PCB_INT_25") (pintype "passive"))
    )
    (net (code "75") (name "unconnected-(U2-TSP_ID-Pad31)") (class "Default")
      (node (ref "U2") (pin "31") (pinfunction "TSP_ID_31") (pintype "passive"))
    )
    (net (code "76") (name "unconnected-(U2-VPP-Pad11)") (class "Default")
      (node (ref "U2") (pin "11") (pinfunction "VPP_11") (pintype "passive"))
    )
  )
)
